# PhaseBLeg.net
KiCad netlist of a schematic drawn in Altium Designer
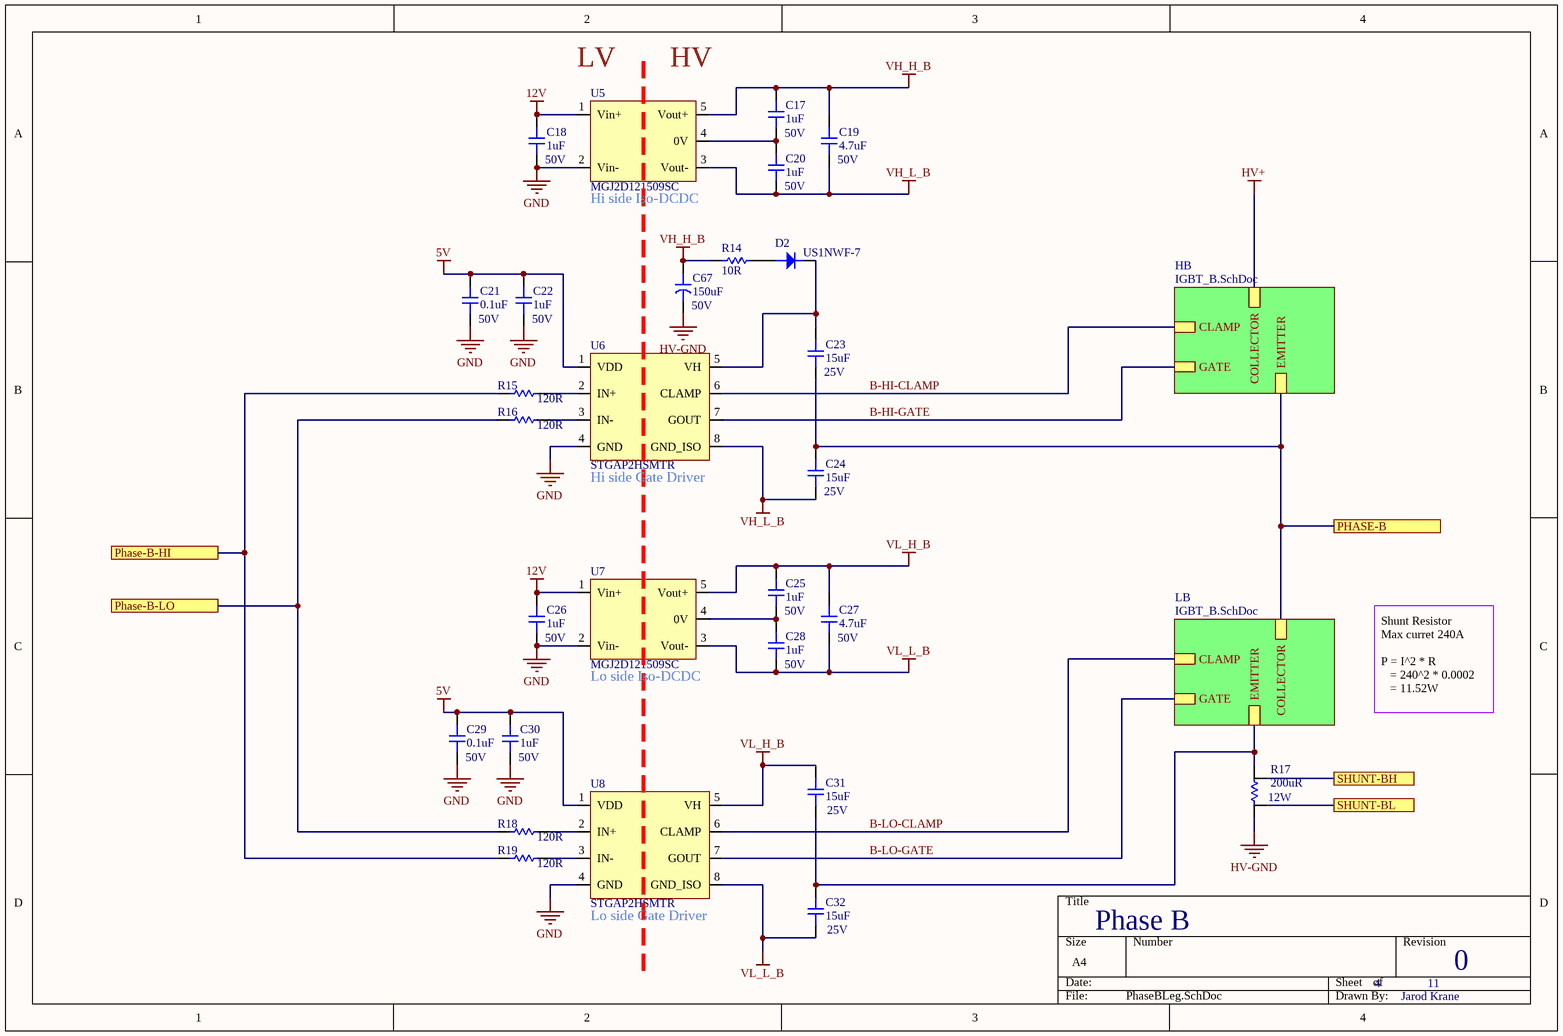
[diagram p0: PhaseBLeg.SchDoc]

(export (version "E")
  (design (tool "Eeschema 10.0.6"))
  (components
    (comp (ref "C17")
      (value "1uF")
      (footprint "CAP-0805")
      (description "CAP CER 1UF 50V X5R 0805")
      (fields
        (field (name "MANUFACTURER") "KEMET")
        (field (name "MANUFACTURER PART NUMBER") "C0805C105K5PACTU")
        (field (name "VOLTAGE RATING") "50V")
      )
      (libsource (lib "InverterSCHLib") (part "0805-1uF-50V"))
    )
    (comp (ref "C18")
      (value "1uF")
      (footprint "CAP-0805")
      (description "CAP CER 1UF 50V X5R 0805")
      (fields
        (field (name "MANUFACTURER") "KEMET")
        (field (name "MANUFACTURER PART NUMBER") "C0805C105K5PACTU")
        (field (name "VOLTAGE RATING") "50V")
      )
      (libsource (lib "InverterSCHLib") (part "0805-1uF-50V"))
    )
    (comp (ref "C19")
      (value "4.7uF")
      (footprint "CAP-1206")
      (description "CAP CER 4.7UF 50V X7R 1206")
      (fields
        (field (name "MANUFACTURER") "TDK")
        (field (name "MANUFACTURER PART NUMBER") "C3216X7R1H475K160AC")
        (field (name "VOLTAGE RATING") "50V")
      )
      (libsource (lib "InverterSCHLib") (part "1206-4.7uF-50V"))
    )
    (comp (ref "C20")
      (value "1uF")
      (footprint "CAP-0805")
      (description "CAP CER 1UF 50V X5R 0805")
      (fields
        (field (name "MANUFACTURER") "KEMET")
        (field (name "MANUFACTURER PART NUMBER") "C0805C105K5PACTU")
        (field (name "VOLTAGE RATING") "50V")
      )
      (libsource (lib "InverterSCHLib") (part "0805-1uF-50V"))
    )
    (comp (ref "C21")
      (value "0.1uF")
      (footprint "CAP-0805")
      (description "CAP CER 0.1UF 50V Y5V 0805")
      (fields
        (field (name "MANUFACTURER") "KEMET")
        (field (name "MANUFACTURER PART NUMBER") "C0805C104Z5VACTU")
        (field (name "VOLTAGE") "50V")
      )
      (libsource (lib "InverterSCHLib") (part "0805-0.1uF-50V"))
    )
    (comp (ref "C22")
      (value "1uF")
      (footprint "CAP-0805")
      (description "CAP CER 1UF 50V X5R 0805")
      (fields
        (field (name "MANUFACTURER") "KEMET")
        (field (name "MANUFACTURER PART NUMBER") "C0805C105K5PACTU")
        (field (name "VOLTAGE RATING") "50V")
      )
      (libsource (lib "InverterSCHLib") (part "0805-1uF-50V"))
    )
    (comp (ref "C23")
      (value "15uF")
      (footprint "CAP-1812")
      (description "CAP CER 15UF 25V X7R 1812")
      (fields
        (field (name "MANUFACTURER") "TDK")
        (field (name "MANUFACTURER PART NUMBER") "C4532X7R1E156M280KB")
        (field (name "VOLTAGE") "25V")
      )
      (libsource (lib "InverterSCHLib") (part "1812-15uF-25V"))
    )
    (comp (ref "C24")
      (value "15uF")
      (footprint "CAP-1812")
      (description "CAP CER 15UF 25V X7R 1812")
      (fields
        (field (name "MANUFACTURER") "TDK")
        (field (name "MANUFACTURER PART NUMBER") "C4532X7R1E156M280KB")
        (field (name "VOLTAGE") "25V")
      )
      (libsource (lib "InverterSCHLib") (part "1812-15uF-25V"))
    )
    (comp (ref "C25")
      (value "1uF")
      (footprint "CAP-0805")
      (description "CAP CER 1UF 50V X5R 0805")
      (fields
        (field (name "MANUFACTURER") "KEMET")
        (field (name "MANUFACTURER PART NUMBER") "C0805C105K5PACTU")
        (field (name "VOLTAGE RATING") "50V")
      )
      (libsource (lib "InverterSCHLib") (part "0805-1uF-50V"))
    )
    (comp (ref "C26")
      (value "1uF")
      (footprint "CAP-0805")
      (description "CAP CER 1UF 50V X5R 0805")
      (fields
        (field (name "MANUFACTURER") "KEMET")
        (field (name "MANUFACTURER PART NUMBER") "C0805C105K5PACTU")
        (field (name "VOLTAGE RATING") "50V")
      )
      (libsource (lib "InverterSCHLib") (part "0805-1uF-50V"))
    )
    (comp (ref "C27")
      (value "4.7uF")
      (footprint "CAP-1206")
      (description "CAP CER 4.7UF 50V X7R 1206")
      (fields
        (field (name "MANUFACTURER") "TDK")
        (field (name "MANUFACTURER PART NUMBER") "C3216X7R1H475K160AC")
        (field (name "VOLTAGE RATING") "50V")
      )
      (libsource (lib "InverterSCHLib") (part "1206-4.7uF-50V"))
    )
    (comp (ref "C28")
      (value "1uF")
      (footprint "CAP-0805")
      (description "CAP CER 1UF 50V X5R 0805")
      (fields
        (field (name "MANUFACTURER") "KEMET")
        (field (name "MANUFACTURER PART NUMBER") "C0805C105K5PACTU")
        (field (name "VOLTAGE RATING") "50V")
      )
      (libsource (lib "InverterSCHLib") (part "0805-1uF-50V"))
    )
    (comp (ref "C29")
      (value "0.1uF")
      (footprint "CAP-0805")
      (description "CAP CER 0.1UF 50V Y5V 0805")
      (fields
        (field (name "MANUFACTURER") "KEMET")
        (field (name "MANUFACTURER PART NUMBER") "C0805C104Z5VACTU")
        (field (name "VOLTAGE") "50V")
      )
      (libsource (lib "InverterSCHLib") (part "0805-0.1uF-50V"))
    )
    (comp (ref "C30")
      (value "1uF")
      (footprint "CAP-0805")
      (description "CAP CER 1UF 50V X5R 0805")
      (fields
        (field (name "MANUFACTURER") "KEMET")
        (field (name "MANUFACTURER PART NUMBER") "C0805C105K5PACTU")
        (field (name "VOLTAGE RATING") "50V")
      )
      (libsource (lib "InverterSCHLib") (part "0805-1uF-50V"))
    )
    (comp (ref "C31")
      (value "15uF")
      (footprint "CAP-1812")
      (description "CAP CER 15UF 25V X7R 1812")
      (fields
        (field (name "MANUFACTURER") "TDK")
        (field (name "MANUFACTURER PART NUMBER") "C4532X7R1E156M280KB")
        (field (name "VOLTAGE") "25V")
      )
      (libsource (lib "InverterSCHLib") (part "1812-15uF-25V"))
    )
    (comp (ref "C32")
      (value "15uF")
      (footprint "CAP-1812")
      (description "CAP CER 15UF 25V X7R 1812")
      (fields
        (field (name "MANUFACTURER") "TDK")
        (field (name "MANUFACTURER PART NUMBER") "C4532X7R1E156M280KB")
        (field (name "VOLTAGE") "25V")
      )
      (libsource (lib "InverterSCHLib") (part "1812-15uF-25V"))
    )
    (comp (ref "C67")
      (value "150uF")
      (footprint "CAPCAN-10mm")
      (description "CAP POLYMER HYBRID 150UF 50V SMD")
      (fields
        (field (name "MANUFACTURER") "Panasonic")
        (field (name "MANUFACTURER PART NUMBER") "EEHZS1H151P")
        (field (name "VOLTAGE") "50V")
      )
      (libsource (lib "InverterSCHLib") (part "10mm-150uF-50V"))
    )
    (comp (ref "D2")
      (value "US1NWF-7")
      (footprint "DIOM2718X12N")
      (description "DIODE GEN PURP 1.2KV 1A SOD123F")
      (fields (field (name "MANUFACTURER") "Diodes"))
      (libsource (lib "InverterSCHLib") (part "Diode 1.2KV-1A"))
    )
    (comp (ref "R14")
      (value "10R")
      (footprint "RES-0603")
      (description "RES SMD 10 OHM 1% 1/10W 0603")
      (fields
        (field (name "MANUFACTURER") "Yageo")
        (field (name "MANUFACTURER PART NUMBER") "RC0603FR-0710RL")
      )
      (libsource (lib "InverterSCHLib") (part "0603-10R"))
    )
    (comp (ref "R15")
      (value "120R")
      (footprint "RES-0603")
      (description "RES SMD 120 OHM 1% 1/10W 0603")
      (fields
        (field (name "MANUFACTURER") "Yageo")
        (field (name "MANUFACTURER PART NUMBER") "RC0603FR-07120RL")
      )
      (libsource (lib "InverterSCHLib") (part "0603-120R"))
    )
    (comp (ref "R16")
      (value "120R")
      (footprint "RES-0603")
      (description "RES SMD 120 OHM 1% 1/10W 0603")
      (fields
        (field (name "MANUFACTURER") "Yageo")
        (field (name "MANUFACTURER PART NUMBER") "RC0603FR-07120RL")
      )
      (libsource (lib "InverterSCHLib") (part "0603-120R"))
    )
    (comp (ref "R17")
      (value "200uR")
      (footprint "RES-SHUNT")
      (description "RES SMD 200 UOHM 1% 12W 3920")
      (fields
        (field (name "MANUFACTURER") "Bourns")
        (field (name "MANUFACTURER PART NUMBER") "CSS2H-3920R-L200FE")
        (field (name "POWER") "12W")
      )
      (libsource (lib "InverterSCHLib") (part "3920-200uR-SHUNT"))
    )
    (comp (ref "R18")
      (value "120R")
      (footprint "RES-0603")
      (description "RES SMD 120 OHM 1% 1/10W 0603")
      (fields
        (field (name "MANUFACTURER") "Yageo")
        (field (name "MANUFACTURER PART NUMBER") "RC0603FR-07120RL")
      )
      (libsource (lib "InverterSCHLib") (part "0603-120R"))
    )
    (comp (ref "R19")
      (value "120R")
      (footprint "RES-0603")
      (description "RES SMD 120 OHM 1% 1/10W 0603")
      (fields
        (field (name "MANUFACTURER") "Yageo")
        (field (name "MANUFACTURER PART NUMBER") "RC0603FR-07120RL")
      )
      (libsource (lib "InverterSCHLib") (part "0603-120R"))
    )
    (comp (ref "U5")
      (value "MGJ2D121509SC")
      (footprint "MGJ2")
      (description "Isolated Module DC DC Converter Output 15V -8.7V - 80mA, 40mA 10.8V - 13.2V Input")
      (fields (field (name "MANUFACTURER") "Murata"))
      (libsource (lib "InverterSCHLib") (part "15V/-8.7V"))
    )
    (comp (ref "U6")
      (value "STGAP2HSMTR")
      (footprint "SO-8W")
      (description "GALVANICALLY ISOLATED 4 A SINGLE GATE DRIVER")
      (fields
        (field (name "MANUFACTURER") "Samtec")
        (field (name "MANUFACTURER PART NUMBER") "ERF8-010-07.0-L-DV-L-K-TR")
      )
      (libsource (lib "InverterSCHLib") (part "STGAP2HSMTR"))
    )
    (comp (ref "U7")
      (value "MGJ2D121509SC")
      (footprint "MGJ2")
      (description "Isolated Module DC DC Converter Output 15V -8.7V - 80mA, 40mA 10.8V - 13.2V Input")
      (fields (field (name "MANUFACTURER") "Murata"))
      (libsource (lib "InverterSCHLib") (part "15V/-8.7V"))
    )
    (comp (ref "U8")
      (value "STGAP2HSMTR")
      (footprint "SO-8W")
      (description "GALVANICALLY ISOLATED 4 A SINGLE GATE DRIVER")
      (fields
        (field (name "MANUFACTURER") "Samtec")
        (field (name "MANUFACTURER PART NUMBER") "ERF8-010-07.0-L-DV-L-K-TR")
      )
      (libsource (lib "InverterSCHLib") (part "STGAP2HSMTR"))
    )
  )
  (nets
    (net (code "1") (name "/B-HI-CLAMP") (class "Default")
      (node (ref "U6") (pin "6") (pinfunction "CLAMP_6") (pintype "passive"))
    )
    (net (code "2") (name "/B-HI-GATE") (class "Default")
      (node (ref "U6") (pin "7") (pinfunction "GOUT_7") (pintype "passive"))
    )
    (net (code "3") (name "/B-LO-CLAMP") (class "Default")
      (node (ref "U8") (pin "6") (pinfunction "CLAMP_6") (pintype "passive"))
    )
    (net (code "4") (name "/B-LO-GATE") (class "Default")
      (node (ref "U8") (pin "7") (pinfunction "GOUT_7") (pintype "passive"))
    )
    (net (code "5") (name "/EMITTER") (class "Default")
      (node (ref "C31") (pin "1") (pinfunction "1_1") (pintype "passive"))
      (node (ref "C32") (pin "2") (pinfunction "2_2") (pintype "passive"))
      (node (ref "R17") (pin "2") (pinfunction "2_2") (pintype "passive"))
    )
    (net (code "6") (name "/PHASE-B") (class "Default")
      (node (ref "C23") (pin "1") (pinfunction "1_1") (pintype "passive"))
      (node (ref "C24") (pin "2") (pinfunction "2_2") (pintype "passive"))
    )
    (net (code "7") (name "/Phase-B-HI") (class "Default")
      (node (ref "R15") (pin "1") (pinfunction "1_1") (pintype "passive"))
      (node (ref "R19") (pin "1") (pinfunction "1_1") (pintype "passive"))
    )
    (net (code "8") (name "/Phase-B-LO") (class "Default")
      (node (ref "R16") (pin "1") (pinfunction "1_1") (pintype "passive"))
      (node (ref "R18") (pin "1") (pinfunction "1_1") (pintype "passive"))
    )
    (net (code "9") (name "/SHUNT-BH") (class "Default")
      (node (ref "R17") (pin "4") (pinfunction "4_4") (pintype "passive"))
    )
    (net (code "10") (name "/SHUNT-BL") (class "Default")
      (node (ref "R17") (pin "3") (pinfunction "3_3") (pintype "passive"))
    )
    (net (code "11") (name "5V") (class "Default")
      (node (ref "C21") (pin "2") (pinfunction "2_2") (pintype "passive"))
      (node (ref "C22") (pin "2") (pinfunction "2_2") (pintype "passive"))
      (node (ref "C29") (pin "2") (pinfunction "2_2") (pintype "passive"))
      (node (ref "C30") (pin "2") (pinfunction "2_2") (pintype "passive"))
      (node (ref "U6") (pin "1") (pinfunction "VDD_1") (pintype "passive"))
      (node (ref "U8") (pin "1") (pinfunction "VDD_1") (pintype "passive"))
    )
    (net (code "12") (name "12V") (class "Default")
      (node (ref "C18") (pin "2") (pinfunction "2_2") (pintype "passive"))
      (node (ref "C26") (pin "2") (pinfunction "2_2") (pintype "passive"))
      (node (ref "U5") (pin "1") (pinfunction "Vin+_1") (pintype "passive"))
      (node (ref "U7") (pin "1") (pinfunction "Vin+_1") (pintype "passive"))
    )
    (net (code "13") (name "GND") (class "Default")
      (node (ref "C18") (pin "1") (pinfunction "1_1") (pintype "passive"))
      (node (ref "C21") (pin "1") (pinfunction "1_1") (pintype "passive"))
      (node (ref "C22") (pin "1") (pinfunction "1_1") (pintype "passive"))
      (node (ref "C26") (pin "1") (pinfunction "1_1") (pintype "passive"))
      (node (ref "C29") (pin "1") (pinfunction "1_1") (pintype "passive"))
      (node (ref "C30") (pin "1") (pinfunction "1_1") (pintype "passive"))
      (node (ref "U5") (pin "2") (pinfunction "Vin-_2") (pintype "passive"))
      (node (ref "U6") (pin "4") (pinfunction "GND_4") (pintype "passive"))
      (node (ref "U7") (pin "2") (pinfunction "Vin-_2") (pintype "passive"))
      (node (ref "U8") (pin "4") (pinfunction "GND_4") (pintype "passive"))
    )
    (net (code "15") (name "HV-GND") (class "Default")
      (node (ref "C67") (pin "2") (pinfunction "2_2") (pintype "passive"))
      (node (ref "R17") (pin "1") (pinfunction "1_1") (pintype "passive"))
    )
    (net (code "16") (name "Net-(D2-Pad2)") (class "Default")
      (node (ref "D2") (pin "2") (pinfunction "2_2") (pintype "passive"))
      (node (ref "R14") (pin "2") (pinfunction "2_2") (pintype "passive"))
    )
    (net (code "17") (name "Net-(U5-0V)") (class "Default")
      (node (ref "C17") (pin "1") (pinfunction "1_1") (pintype "passive"))
      (node (ref "C20") (pin "2") (pinfunction "2_2") (pintype "passive"))
      (node (ref "U5") (pin "4") (pinfunction "0V_4") (pintype "passive"))
    )
    (net (code "18") (name "Net-(U6-IN+)") (class "Default")
      (node (ref "R15") (pin "2") (pinfunction "2_2") (pintype "passive"))
      (node (ref "U6") (pin "2") (pinfunction "IN+_2") (pintype "passive"))
    )
    (net (code "19") (name "Net-(U6-IN-)") (class "Default")
      (node (ref "R16") (pin "2") (pinfunction "2_2") (pintype "passive"))
      (node (ref "U6") (pin "3") (pinfunction "IN-_3") (pintype "passive"))
    )
    (net (code "20") (name "Net-(U6-VH)") (class "Default")
      (node (ref "C23") (pin "2") (pinfunction "2_2") (pintype "passive"))
      (node (ref "D2") (pin "1") (pinfunction "1_1") (pintype "passive"))
      (node (ref "U6") (pin "5") (pinfunction "VH_5") (pintype "passive"))
    )
    (net (code "21") (name "Net-(U7-0V)") (class "Default")
      (node (ref "C25") (pin "1") (pinfunction "1_1") (pintype "passive"))
      (node (ref "C28") (pin "2") (pinfunction "2_2") (pintype "passive"))
      (node (ref "U7") (pin "4") (pinfunction "0V_4") (pintype "passive"))
    )
    (net (code "22") (name "Net-(U8-IN+)") (class "Default")
      (node (ref "R18") (pin "2") (pinfunction "2_2") (pintype "passive"))
      (node (ref "U8") (pin "2") (pinfunction "IN+_2") (pintype "passive"))
    )
    (net (code "23") (name "Net-(U8-IN-)") (class "Default")
      (node (ref "R19") (pin "2") (pinfunction "2_2") (pintype "passive"))
      (node (ref "U8") (pin "3") (pinfunction "IN-_3") (pintype "passive"))
    )
    (net (code "24") (name "VH_H_B") (class "Default")
      (node (ref "C17") (pin "2") (pinfunction "2_2") (pintype "passive"))
      (node (ref "C19") (pin "2") (pinfunction "2_2") (pintype "passive"))
      (node (ref "C67") (pin "1") (pinfunction "1_1") (pintype "passive"))
      (node (ref "R14") (pin "1") (pinfunction "1_1") (pintype "passive"))
      (node (ref "U5") (pin "5") (pinfunction "Vout+_5") (pintype "passive"))
    )
    (net (code "25") (name "VH_L_B") (class "Default")
      (node (ref "C19") (pin "1") (pinfunction "1_1") (pintype "passive"))
      (node (ref "C20") (pin "1") (pinfunction "1_1") (pintype "passive"))
      (node (ref "C24") (pin "1") (pinfunction "1_1") (pintype "passive"))
      (node (ref "U5") (pin "3") (pinfunction "Vout-_3") (pintype "passive"))
      (node (ref "U6") (pin "8") (pinfunction "GND_ISO_8") (pintype "passive"))
    )
    (net (code "26") (name "VL_H_B") (class "Default")
      (node (ref "C25") (pin "2") (pinfunction "2_2") (pintype "passive"))
      (node (ref "C27") (pin "2") (pinfunction "2_2") (pintype "passive"))
      (node (ref "C31") (pin "2") (pinfunction "2_2") (pintype "passive"))
      (node (ref "U7") (pin "5") (pinfunction "Vout+_5") (pintype "passive"))
      (node (ref "U8") (pin "5") (pinfunction "VH_5") (pintype "passive"))
    )
    (net (code "27") (name "VL_L_B") (class "Default")
      (node (ref "C27") (pin "1") (pinfunction "1_1") (pintype "passive"))
      (node (ref "C28") (pin "1") (pinfunction "1_1") (pintype "passive"))
      (node (ref "C32") (pin "1") (pinfunction "1_1") (pintype "passive"))
      (node (ref "U7") (pin "3") (pinfunction "Vout-_3") (pintype "passive"))
      (node (ref "U8") (pin "8") (pinfunction "GND_ISO_8") (pintype "passive"))
    )
  )
)
